# ProPrj_CyberRP_2025-01-25.net
KiCad netlist of a schematic drawn in EasyEDA Pro
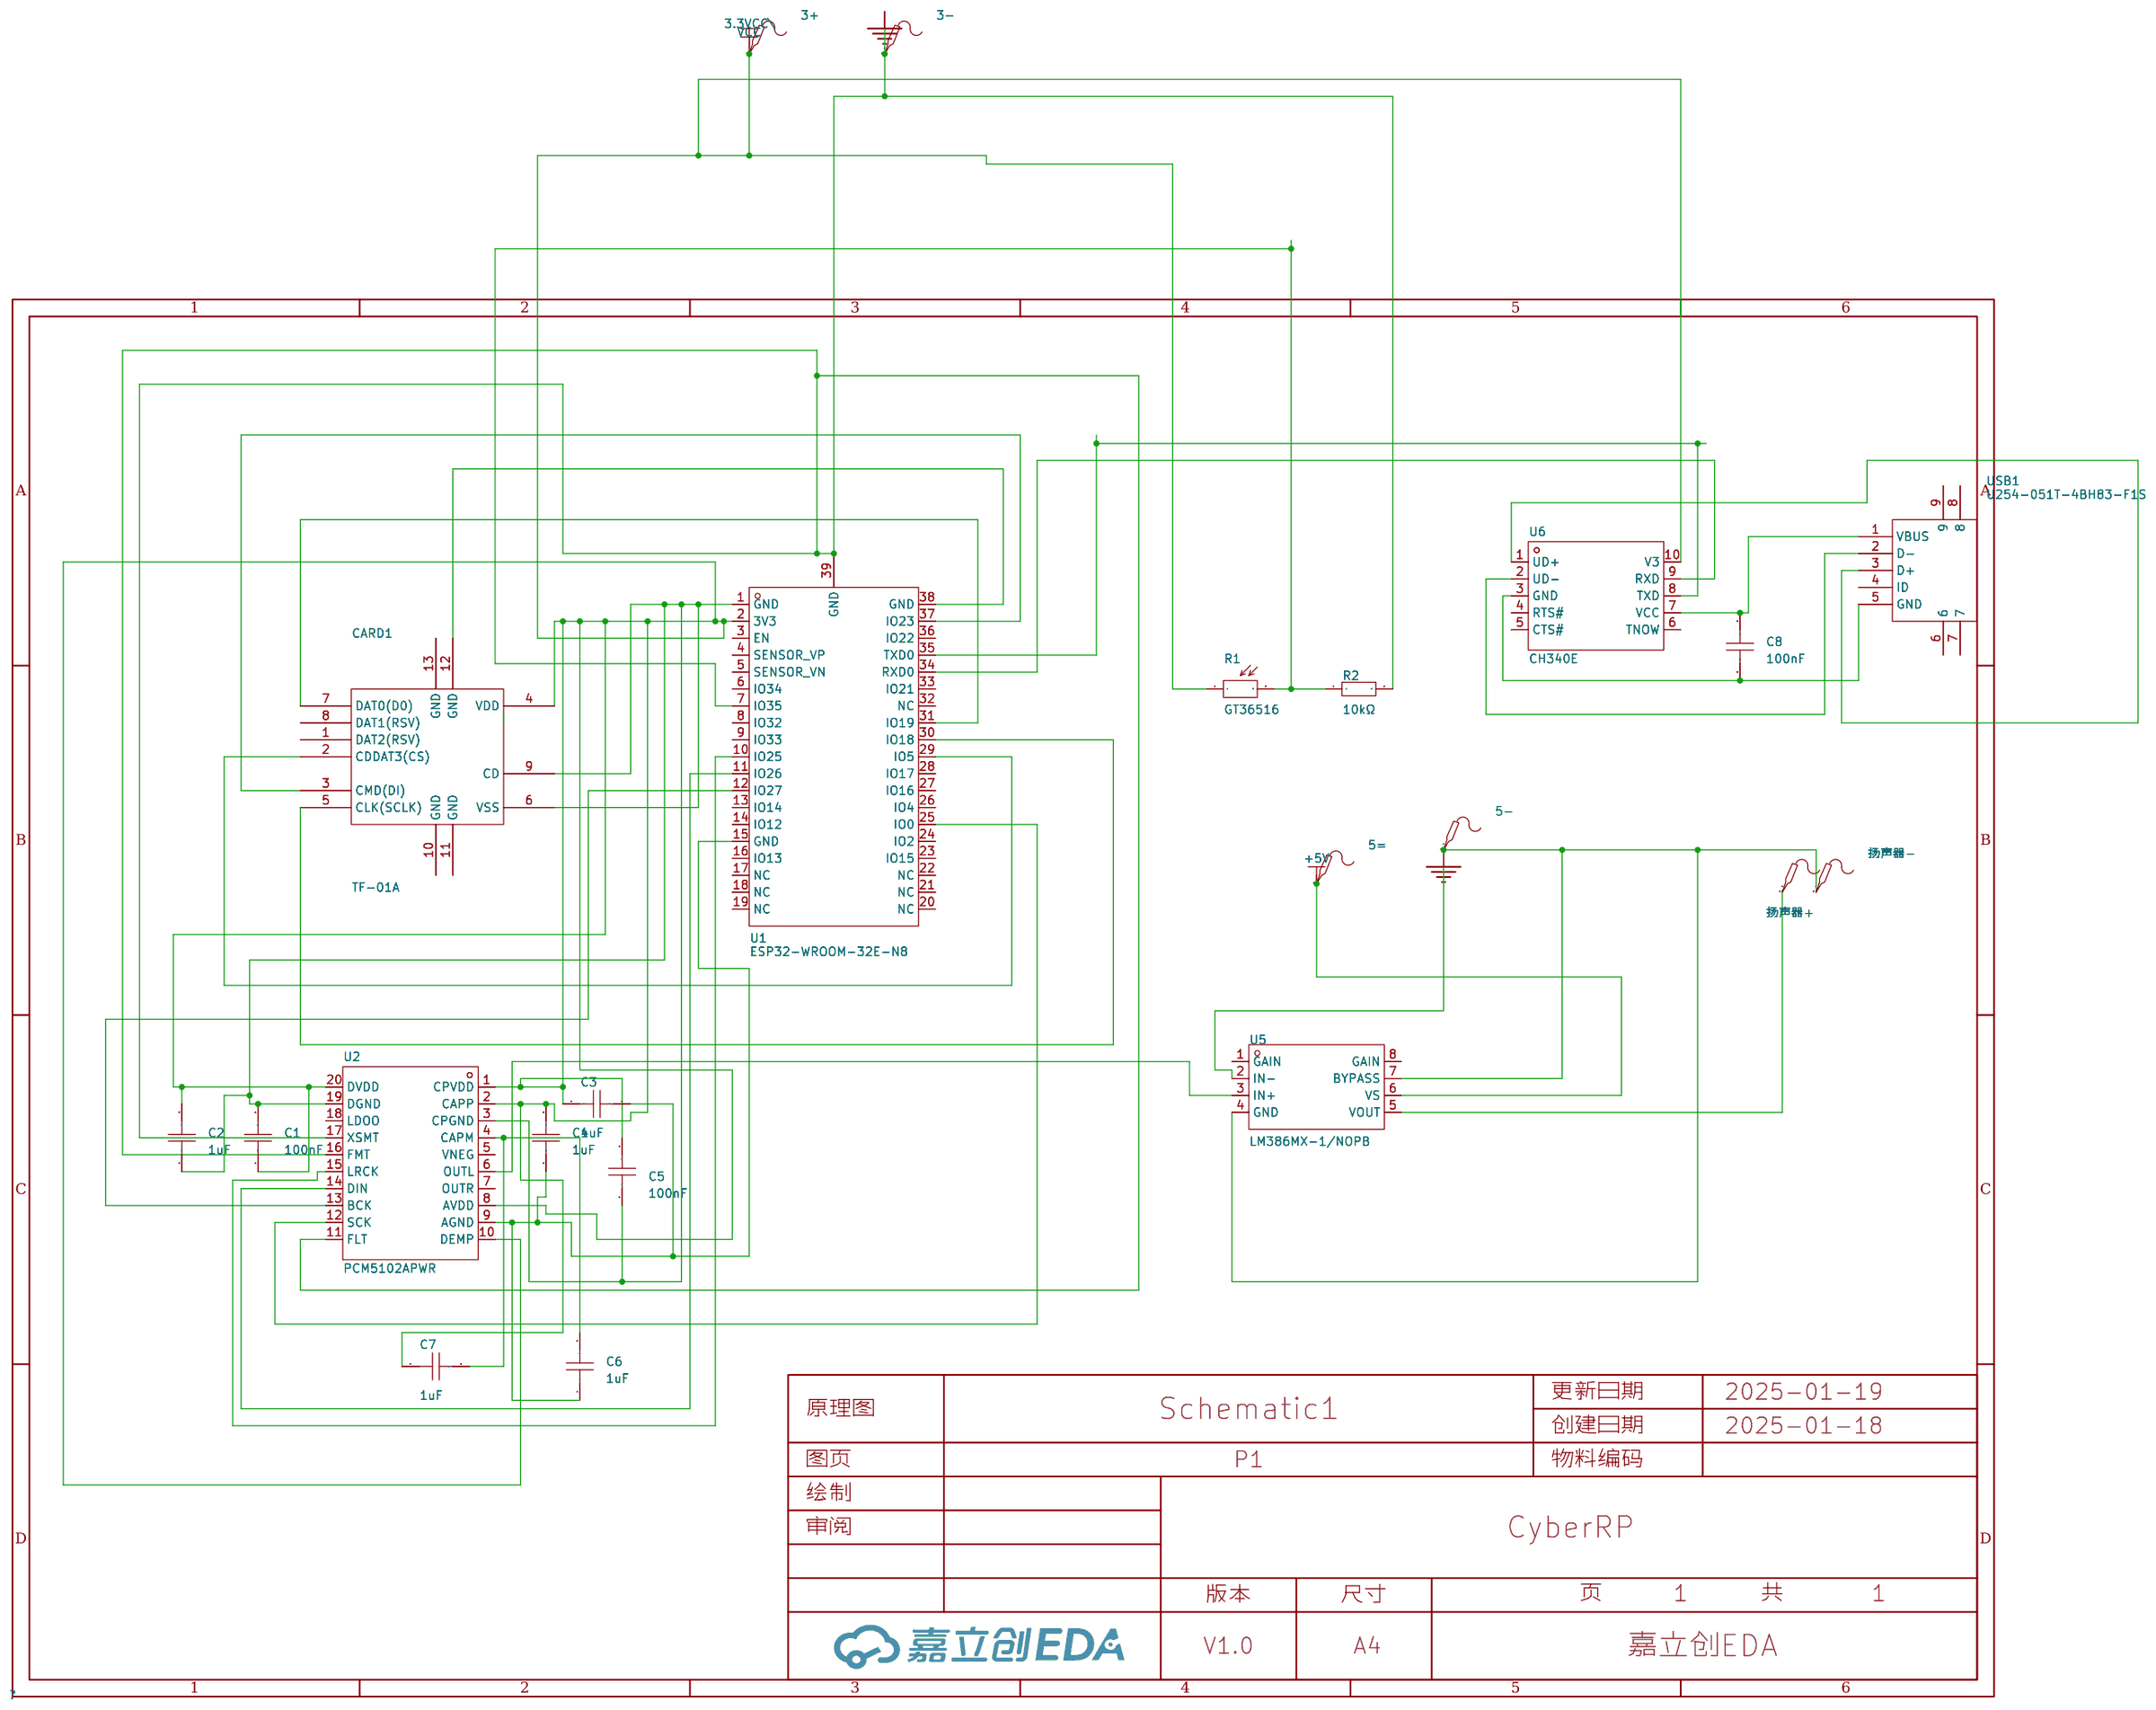
[diagram p0: schematic sheet]

(export (version "E")
  (design (tool "Eeschema 10.0.6"))
  (components
    (comp (ref "3+")
      (value "~")
      (footprint "easyedapro:Test-Point-0.5mm")
      (description "Test Point 测试点")
      (libsource (lib "easyedapro") (part "Test-Point"))
    )
    (comp (ref "3-")
      (value "~")
      (footprint "easyedapro:Test-Point-0.5mm")
      (description "Test Point 测试点")
      (libsource (lib "easyedapro") (part "Test-Point"))
    )
    (comp (ref "5-")
      (value "~")
      (footprint "easyedapro:Test-Point-0.5mm")
      (description "Test Point 测试点")
      (libsource (lib "easyedapro") (part "Test-Point"))
    )
    (comp (ref "5=")
      (value "~")
      (footprint "easyedapro:Test-Point-0.5mm")
      (description "Test Point 测试点")
      (libsource (lib "easyedapro") (part "Test-Point"))
    )
    (comp (ref "C1")
      (value "100nF")
      (footprint "easyedapro:C0603")
      (description "容值:100nF;精度:±10%;额定电压:50V;材质(温度系数):X7R;")
      (fields
        (field (name "Manufacturer Part") "CGA0603X7R104K500JT")
        (field (name "Manufacturer") "HRE(芯声)")
      )
      (libsource (lib "easyedapro") (part "CGA0603X7R104K500JT"))
    )
    (comp (ref "C2")
      (value "1uF")
      (footprint "easyedapro:C0603")
      (description "容值:1uF;精度:±10%;额定电压:50V;材质(温度系数):X5R;")
      (fields
        (field (name "Manufacturer Part") "CL10A105KB8NNNC")
        (field (name "Manufacturer") "SAMSUNG(三星)")
      )
      (libsource (lib "easyedapro") (part "CL10A105KB8NNNC"))
    )
    (comp (ref "C3")
      (value "1uF")
      (footprint "easyedapro:C0603")
      (description "容值:1uF;精度:±10%;额定电压:50V;材质(温度系数):X5R;")
      (fields
        (field (name "Manufacturer Part") "CL10A105KB8NNNC")
        (field (name "Manufacturer") "SAMSUNG(三星)")
      )
      (libsource (lib "easyedapro") (part "CL10A105KB8NNNC"))
    )
    (comp (ref "C4")
      (value "1uF")
      (footprint "easyedapro:C0603")
      (description "容值:1uF;精度:±10%;额定电压:50V;材质(温度系数):X5R;")
      (fields
        (field (name "Manufacturer Part") "CL10A105KB8NNNC")
        (field (name "Manufacturer") "SAMSUNG(三星)")
      )
      (libsource (lib "easyedapro") (part "CL10A105KB8NNNC"))
    )
    (comp (ref "C5")
      (value "100nF")
      (footprint "easyedapro:C0603")
      (description "容值:100nF;精度:±10%;额定电压:50V;材质(温度系数):X7R;")
      (fields
        (field (name "Manufacturer Part") "CL10B104KB8NNNC")
        (field (name "Manufacturer") "SAMSUNG(三星)")
      )
      (libsource (lib "easyedapro") (part "CL10B104KB8NNNC"))
    )
    (comp (ref "C6")
      (value "1uF")
      (footprint "easyedapro:C0603")
      (description "容值:1uF;精度:±10%;额定电压:50V;材质(温度系数):X5R;")
      (fields
        (field (name "Manufacturer Part") "CL10A105KB8NNNC")
        (field (name "Manufacturer") "SAMSUNG(三星)")
      )
      (libsource (lib "easyedapro") (part "CL10A105KB8NNNC"))
    )
    (comp (ref "C7")
      (value "1uF")
      (footprint "easyedapro:C0603")
      (description "容值:1uF;精度:±10%;额定电压:50V;材质(温度系数):X5R;")
      (fields
        (field (name "Manufacturer Part") "CL10A105KB8NNNC")
        (field (name "Manufacturer") "SAMSUNG(三星)")
      )
      (libsource (lib "easyedapro") (part "CL10A105KB8NNNC"))
    )
    (comp (ref "C8")
      (value "100nF")
      (footprint "easyedapro:C0603")
      (description "容值:100nF;精度:±10%;额定电压:50V;材质(温度系数):X7R;")
      (fields
        (field (name "Manufacturer Part") "CGA0603X7R104K500JT")
        (field (name "Manufacturer") "HRE(芯声)")
      )
      (libsource (lib "easyedapro") (part "CGA0603X7R104K500JT"))
    )
    (comp (ref "CARD1")
      (value "TF-01A")
      (footprint "easyedapro:TF-SMD_TF-01A")
      (description "卡连接方式:自弹式;卡类型:MicroSD卡(TF卡);连接器类型:卡座;本体最大高度:1.85mm;工作温度范围:-;")
      (fields (field (name "Manufacturer") "韩国韩荣"))
      (libsource (lib "easyedapro") (part "TF-01A"))
    )
    (comp (ref "R1")
      (value "GT36516")
      (footprint "easyedapro:RES-SMD_L3.6-W2.4")
      (description "光敏电阻")
      (fields (field (name "Manufacturer") "JCHL(晶创和立)"))
      (libsource (lib "easyedapro") (part "GT36516"))
    )
    (comp (ref "R2")
      (value "10kΩ")
      (footprint "easyedapro:R0603")
      (description "电阻类型:厚膜电阻;阻值:10kΩ;精度:±1%;功率:100mW;最大工作电压:75V;温度系数:±100ppm/°C;")
      (fields
        (field (name "Manufacturer Part") "0603WAF1002T5E")
        (field (name "Manufacturer") "UNI-ROYAL(厚声)")
      )
      (libsource (lib "easyedapro") (part "0603WAF1002T5E"))
    )
    (comp (ref "U1")
      (value "ESP32-WROOM-32E-N8")
      (footprint "easyedapro:WIFI-SMD_ESP32-WROOM-32E")
      (description "ESP32-WROOM-32E 集成 ESP32-D0WD-V3 芯片，具有?高的稳定性和安全性能。")
      (fields (field (name "Manufacturer") "ESPRESSIF(乐鑫)"))
      (libsource (lib "easyedapro") (part "ESP32-WROOM-32E(8MB)"))
    )
    (comp (ref "U2")
      (value "PCM5102APWR")
      (footprint "easyedapro:TSSOP-20_L6.5-W4.4-P0.65-LS6.4-BL")
      (description "接口类型:PCM;供电电压:1.65V~3.46V;分辨率(位):24；16；32;")
      (fields (field (name "Manufacturer") "TI(德州仪器)"))
      (libsource (lib "easyedapro") (part "PCM5102APWR"))
    )
    (comp (ref "U5")
      (value "LM386MX-1/NOPB")
      (footprint "easyedapro:SOIC-8_L4.9-W3.9-P1.27-LS6.0-BL")
      (description "功放类型:AB类功放;扬声器通道数:单声道;输出功率:325mWx1@8Ω;")
      (fields (field (name "Manufacturer") "TI(德州仪器)"))
      (libsource (lib "easyedapro") (part "LM386MX-1/NOPB"))
    )
    (comp (ref "U6")
      (value "CH340E")
      (footprint "easyedapro:MSOP-10_L3.0-W3.0-P0.50-LS5.0-BL")
      (description "应用功能:收发器;接口协议:USB 2.0;数据速率:2Mbps;")
      (fields (field (name "Manufacturer") "WCH(南京沁恒)"))
      (libsource (lib "easyedapro") (part "CH340E"))
    )
    (comp (ref "USB1")
      (value "U254-051T-4BH83-F1S")
      (footprint "easyedapro:MICRO-USB-SMD_U254-051T-4BH83-F1S")
      (fields (field (name "Manufacturer") "XKB Connection(中国星坤)"))
      (libsource (lib "easyedapro") (part "U254-051T-4BH83-F1S"))
    )
    (comp (ref "扬声器+")
      (value "~")
      (footprint "easyedapro:Test-Point-0.5mm")
      (description "Test Point 测试点")
      (libsource (lib "easyedapro") (part "Test-Point"))
    )
    (comp (ref "扬声器-")
      (value "~")
      (footprint "easyedapro:Test-Point-0.5mm")
      (description "Test Point 测试点")
      (libsource (lib "easyedapro") (part "Test-Point"))
    )
  )
  (nets
    (net (code "1") (name "+5V") (class "Default")
      (node (ref "5=") (pin "1") (pinfunction "1_1") (pintype "input"))
      (node (ref "U5") (pin "6") (pinfunction "VS_6") (pintype "unspecified"))
    )
    (net (code "2") (name "3.3GND") (class "Default")
      (node (ref "3-") (pin "1") (pinfunction "1_1") (pintype "input"))
      (node (ref "R2") (pin "2") (pinfunction "2_2") (pintype "input"))
      (node (ref "U1") (pin "39") (pinfunction "GND_39") (pintype "unspecified"))
      (node (ref "U2") (pin "11") (pinfunction "FLT_11") (pintype "unspecified"))
      (node (ref "U2") (pin "16") (pinfunction "FMT_16") (pintype "unspecified"))
      (node (ref "U2") (pin "17") (pinfunction "XSMT_17") (pintype "unspecified"))
    )
    (net (code "4") (name "GND") (class "Default")
      (node (ref "5-") (pin "1") (pinfunction "1_1") (pintype "input"))
      (node (ref "U5") (pin "2") (pinfunction "IN-_2") (pintype "unspecified"))
      (node (ref "U5") (pin "4") (pinfunction "GND_4") (pintype "unspecified"))
      (node (ref "U5") (pin "7") (pinfunction "BYPASS_7") (pintype "unspecified"))
      (node (ref "扬声器-") (pin "1") (pinfunction "1_1") (pintype "input"))
    )
    (net (code "5") (name "Net-(CARD1-CD)") (class "Default")
      (node (ref "C1") (pin "2") (pinfunction "2_2") (pintype "unspecified"))
      (node (ref "C2") (pin "1") (pinfunction "1_1") (pintype "unspecified"))
      (node (ref "C5") (pin "2") (pinfunction "2_2") (pintype "unspecified"))
      (node (ref "CARD1") (pin "6") (pinfunction "VSS_6") (pintype "input"))
      (node (ref "CARD1") (pin "9") (pinfunction "CD_9") (pintype "input"))
      (node (ref "U1") (pin "1") (pinfunction "GND_1") (pintype "unspecified"))
      (node (ref "U2") (pin "19") (pinfunction "DGND_19") (pintype "unspecified"))
      (node (ref "U2") (pin "3") (pinfunction "CPGND_3") (pintype "unspecified"))
    )
    (net (code "6") (name "Net-(CARD1-CDDAT3(CS))") (class "Default")
      (node (ref "CARD1") (pin "2") (pinfunction "CDDAT3(CS)_2") (pintype "bidirectional"))
      (node (ref "U1") (pin "29") (pinfunction "IO5_29") (pintype "unspecified"))
    )
    (net (code "7") (name "Net-(CARD1-CLK(SCLK))") (class "Default")
      (node (ref "CARD1") (pin "5") (pinfunction "CLK(SCLK)_5") (pintype "input"))
      (node (ref "U1") (pin "30") (pinfunction "IO18_30") (pintype "unspecified"))
    )
    (net (code "8") (name "Net-(CARD1-CMD(DI))") (class "Default")
      (node (ref "CARD1") (pin "3") (pinfunction "CMD(DI)_3") (pintype "input"))
      (node (ref "U1") (pin "37") (pinfunction "IO23_37") (pintype "unspecified"))
    )
    (net (code "9") (name "Net-(CARD1-DAT0(D0))") (class "Default")
      (node (ref "CARD1") (pin "7") (pinfunction "DAT0(D0)_7") (pintype "bidirectional"))
      (node (ref "U1") (pin "31") (pinfunction "IO19_31") (pintype "unspecified"))
    )
    (net (code "10") (name "Net-(CARD1-GND-Pad12)") (class "Default")
      (node (ref "CARD1") (pin "12") (pinfunction "GND_12") (pintype "input"))
      (node (ref "U1") (pin "38") (pinfunction "GND_38") (pintype "unspecified"))
    )
    (net (code "11") (name "Net-(U1-IO0)") (class "Default")
      (node (ref "U1") (pin "25") (pinfunction "IO0_25") (pintype "unspecified"))
      (node (ref "U2") (pin "12") (pinfunction "SCK_12") (pintype "unspecified"))
    )
    (net (code "12") (name "Net-(U1-IO25)") (class "Default")
      (node (ref "U1") (pin "10") (pinfunction "IO25_10") (pintype "unspecified"))
      (node (ref "U2") (pin "15") (pinfunction "LRCK_15") (pintype "unspecified"))
    )
    (net (code "13") (name "Net-(U1-IO26)") (class "Default")
      (node (ref "U1") (pin "11") (pinfunction "IO26_11") (pintype "unspecified"))
      (node (ref "U2") (pin "14") (pinfunction "DIN_14") (pintype "unspecified"))
    )
    (net (code "14") (name "Net-(U1-IO27)") (class "Default")
      (node (ref "U1") (pin "12") (pinfunction "IO27_12") (pintype "unspecified"))
      (node (ref "U2") (pin "13") (pinfunction "BCK_13") (pintype "unspecified"))
    )
    (net (code "15") (name "Net-(U1-IO35)") (class "Default")
      (node (ref "R1") (pin "2") (pinfunction "2_2") (pintype "unspecified"))
      (node (ref "R2") (pin "1") (pinfunction "1_1") (pintype "input"))
      (node (ref "U1") (pin "7") (pinfunction "IO35_7") (pintype "unspecified"))
    )
    (net (code "16") (name "Net-(U1-RXD0)") (class "Default")
      (node (ref "U1") (pin "34") (pinfunction "RXD0_34") (pintype "unspecified"))
      (node (ref "U6") (pin "9") (pinfunction "RXD_9") (pintype "unspecified"))
    )
    (net (code "17") (name "Net-(U1-TXD0)") (class "Default")
      (node (ref "U1") (pin "35") (pinfunction "TXD0_35") (pintype "unspecified"))
      (node (ref "U6") (pin "8") (pinfunction "TXD_8") (pintype "unspecified"))
    )
    (net (code "18") (name "Net-(U2-AGND)") (class "Default")
      (node (ref "C3") (pin "2") (pinfunction "2_2") (pintype "unspecified"))
      (node (ref "C4") (pin "1") (pinfunction "1_1") (pintype "unspecified"))
      (node (ref "C6") (pin "1") (pinfunction "1_1") (pintype "unspecified"))
      (node (ref "U1") (pin "15") (pinfunction "GND_15") (pintype "unspecified"))
      (node (ref "U2") (pin "9") (pinfunction "AGND_9") (pintype "unspecified"))
    )
    (net (code "19") (name "Net-(U2-CAPM)") (class "Default")
      (node (ref "C6") (pin "2") (pinfunction "2_2") (pintype "unspecified"))
      (node (ref "C7") (pin "2") (pinfunction "2_2") (pintype "unspecified"))
      (node (ref "U2") (pin "4") (pinfunction "CAPM_4") (pintype "unspecified"))
    )
    (net (code "20") (name "Net-(U2-OUTL)") (class "Default")
      (node (ref "U2") (pin "6") (pinfunction "OUTL_6") (pintype "unspecified"))
      (node (ref "U5") (pin "3") (pinfunction "IN+_3") (pintype "unspecified"))
    )
    (net (code "21") (name "Net-(U5-VOUT)") (class "Default")
      (node (ref "U5") (pin "5") (pinfunction "VOUT_5") (pintype "unspecified"))
      (node (ref "扬声器+") (pin "1") (pinfunction "1_1") (pintype "input"))
    )
    (net (code "22") (name "Net-(U6-GND)") (class "Default")
      (node (ref "C8") (pin "1") (pinfunction "1_1") (pintype "unspecified"))
      (node (ref "U6") (pin "3") (pinfunction "GND_3") (pintype "unspecified"))
      (node (ref "USB1") (pin "5") (pinfunction "GND_5") (pintype "unspecified"))
    )
    (net (code "23") (name "Net-(U6-UD+)") (class "Default")
      (node (ref "U6") (pin "1") (pinfunction "UD+_1") (pintype "unspecified"))
      (node (ref "USB1") (pin "3") (pinfunction "D+_3") (pintype "unspecified"))
    )
    (net (code "24") (name "Net-(U6-UD-)") (class "Default")
      (node (ref "U6") (pin "2") (pinfunction "UD-_2") (pintype "unspecified"))
      (node (ref "USB1") (pin "2") (pinfunction "D-_2") (pintype "unspecified"))
    )
    (net (code "25") (name "Net-(U6-VCC)") (class "Default")
      (node (ref "C8") (pin "2") (pinfunction "2_2") (pintype "unspecified"))
      (node (ref "U6") (pin "7") (pinfunction "VCC_7") (pintype "unspecified"))
      (node (ref "USB1") (pin "1") (pinfunction "VBUS_1") (pintype "unspecified"))
    )
    (net (code "26") (name "VCC") (class "Default")
      (node (ref "3+") (pin "1") (pinfunction "1_1") (pintype "input"))
      (node (ref "C1") (pin "1") (pinfunction "1_1") (pintype "unspecified"))
      (node (ref "C2") (pin "2") (pinfunction "2_2") (pintype "unspecified"))
      (node (ref "C3") (pin "1") (pinfunction "1_1") (pintype "unspecified"))
      (node (ref "C4") (pin "2") (pinfunction "2_2") (pintype "unspecified"))
      (node (ref "C5") (pin "1") (pinfunction "1_1") (pintype "unspecified"))
      (node (ref "C7") (pin "1") (pinfunction "1_1") (pintype "unspecified"))
      (node (ref "CARD1") (pin "4") (pinfunction "VDD_4") (pintype "input"))
      (node (ref "R1") (pin "1") (pinfunction "1_1") (pintype "unspecified"))
      (node (ref "U1") (pin "2") (pinfunction "3V3_2") (pintype "unspecified"))
      (node (ref "U2") (pin "1") (pinfunction "CPVDD_1") (pintype "unspecified"))
      (node (ref "U2") (pin "10") (pinfunction "DEMP_10") (pintype "unspecified"))
      (node (ref "U2") (pin "2") (pinfunction "CAPP_2") (pintype "unspecified"))
      (node (ref "U2") (pin "20") (pinfunction "DVDD_20") (pintype "unspecified"))
      (node (ref "U2") (pin "8") (pinfunction "AVDD_8") (pintype "unspecified"))
      (node (ref "U6") (pin "10") (pinfunction "V3_10") (pintype "unspecified"))
    )
    (net (code "27") (name "unconnected-(CARD1-DAT1(RSV)-Pad8)") (class "Default")
      (node (ref "CARD1") (pin "8") (pinfunction "DAT1(RSV)_8") (pintype "bidirectional"))
    )
    (net (code "28") (name "unconnected-(CARD1-DAT2(RSV)-Pad1)") (class "Default")
      (node (ref "CARD1") (pin "1") (pinfunction "DAT2(RSV)_1") (pintype "bidirectional"))
    )
    (net (code "29") (name "unconnected-(CARD1-GND-Pad10)") (class "Default")
      (node (ref "CARD1") (pin "10") (pinfunction "GND_10") (pintype "input"))
    )
    (net (code "30") (name "unconnected-(CARD1-GND-Pad11)") (class "Default")
      (node (ref "CARD1") (pin "11") (pinfunction "GND_11") (pintype "input"))
    )
    (net (code "31") (name "unconnected-(CARD1-GND-Pad13)") (class "Default")
      (node (ref "CARD1") (pin "13") (pinfunction "GND_13") (pintype "input"))
    )
    (net (code "32") (name "unconnected-(U1-EN-Pad3)") (class "Default")
      (node (ref "U1") (pin "3") (pinfunction "EN_3") (pintype "unspecified"))
    )
    (net (code "33") (name "unconnected-(U1-IO2-Pad24)") (class "Default")
      (node (ref "U1") (pin "24") (pinfunction "IO2_24") (pintype "unspecified"))
    )
    (net (code "34") (name "unconnected-(U1-IO4-Pad26)") (class "Default")
      (node (ref "U1") (pin "26") (pinfunction "IO4_26") (pintype "unspecified"))
    )
    (net (code "35") (name "unconnected-(U1-IO12-Pad14)") (class "Default")
      (node (ref "U1") (pin "14") (pinfunction "IO12_14") (pintype "unspecified"))
    )
    (net (code "36") (name "unconnected-(U1-IO13-Pad16)") (class "Default")
      (node (ref "U1") (pin "16") (pinfunction "IO13_16") (pintype "unspecified"))
    )
    (net (code "37") (name "unconnected-(U1-IO14-Pad13)") (class "Default")
      (node (ref "U1") (pin "13") (pinfunction "IO14_13") (pintype "unspecified"))
    )
    (net (code "38") (name "unconnected-(U1-IO15-Pad23)") (class "Default")
      (node (ref "U1") (pin "23") (pinfunction "IO15_23") (pintype "unspecified"))
    )
    (net (code "39") (name "unconnected-(U1-IO16-Pad27)") (class "Default")
      (node (ref "U1") (pin "27") (pinfunction "IO16_27") (pintype "unspecified"))
    )
    (net (code "40") (name "unconnected-(U1-IO17-Pad28)") (class "Default")
      (node (ref "U1") (pin "28") (pinfunction "IO17_28") (pintype "unspecified"))
    )
    (net (code "41") (name "unconnected-(U1-IO21-Pad33)") (class "Default")
      (node (ref "U1") (pin "33") (pinfunction "IO21_33") (pintype "unspecified"))
    )
    (net (code "42") (name "unconnected-(U1-IO22-Pad36)") (class "Default")
      (node (ref "U1") (pin "36") (pinfunction "IO22_36") (pintype "unspecified"))
    )
    (net (code "43") (name "unconnected-(U1-IO32-Pad8)") (class "Default")
      (node (ref "U1") (pin "8") (pinfunction "IO32_8") (pintype "unspecified"))
    )
    (net (code "44") (name "unconnected-(U1-IO33-Pad9)") (class "Default")
      (node (ref "U1") (pin "9") (pinfunction "IO33_9") (pintype "unspecified"))
    )
    (net (code "45") (name "unconnected-(U1-IO34-Pad6)") (class "Default")
      (node (ref "U1") (pin "6") (pinfunction "IO34_6") (pintype "unspecified"))
    )
    (net (code "46") (name "unconnected-(U1-NC-Pad17)") (class "Default")
      (node (ref "U1") (pin "17") (pinfunction "NC_17") (pintype "unspecified"))
    )
    (net (code "47") (name "unconnected-(U1-NC-Pad18)") (class "Default")
      (node (ref "U1") (pin "18") (pinfunction "NC_18") (pintype "unspecified"))
    )
    (net (code "48") (name "unconnected-(U1-NC-Pad19)") (class "Default")
      (node (ref "U1") (pin "19") (pinfunction "NC_19") (pintype "unspecified"))
    )
    (net (code "49") (name "unconnected-(U1-NC-Pad20)") (class "Default")
      (node (ref "U1") (pin "20") (pinfunction "NC_20") (pintype "unspecified"))
    )
    (net (code "50") (name "unconnected-(U1-NC-Pad21)") (class "Default")
      (node (ref "U1") (pin "21") (pinfunction "NC_21") (pintype "unspecified"))
    )
    (net (code "51") (name "unconnected-(U1-NC-Pad22)") (class "Default")
      (node (ref "U1") (pin "22") (pinfunction "NC_22") (pintype "unspecified"))
    )
    (net (code "52") (name "unconnected-(U1-NC-Pad32)") (class "Default")
      (node (ref "U1") (pin "32") (pinfunction "NC_32") (pintype "unspecified"))
    )
    (net (code "53") (name "unconnected-(U1-SENSOR_VN-Pad5)") (class "Default")
      (node (ref "U1") (pin "5") (pinfunction "SENSOR_VN_5") (pintype "unspecified"))
    )
    (net (code "54") (name "unconnected-(U1-SENSOR_VP-Pad4)") (class "Default")
      (node (ref "U1") (pin "4") (pinfunction "SENSOR_VP_4") (pintype "unspecified"))
    )
    (net (code "55") (name "unconnected-(U2-LDOO-Pad18)") (class "Default")
      (node (ref "U2") (pin "18") (pinfunction "LDOO_18") (pintype "unspecified"))
    )
    (net (code "56") (name "unconnected-(U2-OUTR-Pad7)") (class "Default")
      (node (ref "U2") (pin "7") (pinfunction "OUTR_7") (pintype "unspecified"))
    )
    (net (code "57") (name "unconnected-(U2-VNEG-Pad5)") (class "Default")
      (node (ref "U2") (pin "5") (pinfunction "VNEG_5") (pintype "unspecified"))
    )
    (net (code "58") (name "unconnected-(U5-GAIN-Pad1)") (class "Default")
      (node (ref "U5") (pin "1") (pinfunction "GAIN_1") (pintype "unspecified"))
    )
    (net (code "59") (name "unconnected-(U5-GAIN-Pad8)") (class "Default")
      (node (ref "U5") (pin "8") (pinfunction "GAIN_8") (pintype "unspecified"))
    )
    (net (code "60") (name "unconnected-(U6-CTS#-Pad5)") (class "Default")
      (node (ref "U6") (pin "5") (pinfunction "CTS#_5") (pintype "unspecified"))
    )
    (net (code "61") (name "unconnected-(U6-RTS#-Pad4)") (class "Default")
      (node (ref "U6") (pin "4") (pinfunction "RTS#_4") (pintype "unspecified"))
    )
    (net (code "62") (name "unconnected-(U6-TNOW-Pad6)") (class "Default")
      (node (ref "U6") (pin "6") (pinfunction "TNOW_6") (pintype "unspecified"))
    )
    (net (code "63") (name "unconnected-(USB1-ID-Pad4)") (class "Default")
      (node (ref "USB1") (pin "4") (pinfunction "ID_4") (pintype "unspecified"))
    )
    (net (code "64") (name "unconnected-(USB1-Pad6)") (class "Default")
      (node (ref "USB1") (pin "6") (pinfunction "6_6") (pintype "unspecified"))
    )
    (net (code "65") (name "unconnected-(USB1-Pad7)") (class "Default")
      (node (ref "USB1") (pin "7") (pinfunction "7_7") (pintype "unspecified"))
    )
    (net (code "66") (name "unconnected-(USB1-Pad8)") (class "Default")
      (node (ref "USB1") (pin "8") (pinfunction "8_8") (pintype "unspecified"))
    )
    (net (code "67") (name "unconnected-(USB1-Pad9)") (class "Default")
      (node (ref "USB1") (pin "9") (pinfunction "9_9") (pintype "unspecified"))
    )
  )
)
